# usb_to_uart.net
KiCad netlist of a schematic drawn in Altium Designer
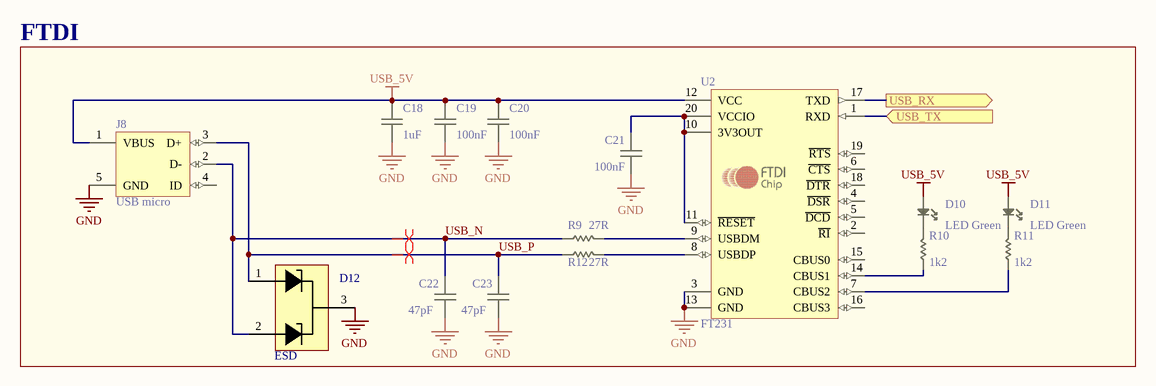
[diagram p0: usb to uart.SchDoc]

(export (version "E")
  (design (tool "Eeschema 10.0.6"))
  (components
    (comp (ref "C18")
      (value "1uF")
      (footprint "C0603")
      (fields (field (name "Comment") "Capacitor 0603"))
      (libsource (lib "altium-import") (part "root_1_Capacitor 0603_"))
    )
    (comp (ref "C19")
      (value "100nF")
      (footprint "C0603")
      (fields (field (name "Comment") "Capacitor 0603"))
      (libsource (lib "altium-import") (part "root_1_Capacitor 0603_"))
    )
    (comp (ref "C20")
      (value "100nF")
      (footprint "C0603")
      (fields (field (name "Comment") "Capacitor 0603"))
      (libsource (lib "altium-import") (part "root_1_Capacitor 0603_"))
    )
    (comp (ref "C21")
      (value "100nF")
      (footprint "C0603")
      (fields (field (name "Comment") "Capacitor 0603"))
      (libsource (lib "altium-import") (part "root_1_Capacitor 0603_"))
    )
    (comp (ref "C22")
      (value "47pF")
      (footprint "C0603")
      (fields (field (name "Comment") "Capacitor 0603"))
      (libsource (lib "altium-import") (part "root_1_Capacitor 0603_"))
    )
    (comp (ref "C23")
      (value "47pF")
      (footprint "C0603")
      (fields (field (name "Comment") "Capacitor 0603"))
      (libsource (lib "altium-import") (part "root_1_Capacitor 0603_"))
    )
    (comp (ref "D10")
      (value "LED Green")
      (footprint "L0603 GREEN")
      (libsource (lib "altium-import") (part "root_3_LED 0603 Green_"))
    )
    (comp (ref "D11")
      (value "LED Green")
      (footprint "L0603 GREEN")
      (libsource (lib "altium-import") (part "root_3_LED 0603 Green_"))
    )
    (comp (ref "D12")
      (value "ESD")
      (footprint "ESD protection")
      (description "PESD3V3S2UAT")
      (libsource (lib "Transistors") (part "ESD protection 3.3V"))
    )
    (comp (ref "J8")
      (value "USB micro")
      (footprint "USB micro")
      (libsource (lib "altium-import") (part "root_0_USB micro_"))
    )
    (comp (ref "R9")
      (value "27R")
      (footprint "R0603")
      (fields (field (name "Comment") "Resistor 0603"))
      (libsource (lib "altium-import") (part "root_0_Resistor 0603_"))
    )
    (comp (ref "R10")
      (value "1k2")
      (footprint "R0603")
      (fields (field (name "Comment") "Resistor 0603"))
      (libsource (lib "altium-import") (part "root_1_Resistor 0603_"))
    )
    (comp (ref "R11")
      (value "1k2")
      (footprint "R0603")
      (fields (field (name "Comment") "Resistor 0603"))
      (libsource (lib "altium-import") (part "root_1_Resistor 0603_"))
    )
    (comp (ref "R12")
      (value "27R")
      (footprint "R0603")
      (fields (field (name "Comment") "Resistor 0603"))
      (libsource (lib "altium-import") (part "root_0_Resistor 0603_"))
    )
    (comp (ref "U2")
      (value "FT231")
      (footprint "FTDI")
      (description "USB to UART")
      (libsource (lib "altium-import") (part "root_0_FTDI_"))
    )
  )
  (nets
    (net (code "1") (name "/USB_N") (class "Default")
      (node (ref "C22") (pin "2") (pinfunction "2_2") (pintype "passive"))
      (node (ref "D12") (pin "2") (pintype "passive"))
      (node (ref "J8") (pin "2") (pinfunction "D-_2") (pintype "bidirectional"))
      (node (ref "R9") (pin "1") (pinfunction "1_1") (pintype "passive"))
    )
    (net (code "2") (name "/USB_P") (class "Default")
      (node (ref "C23") (pin "2") (pinfunction "2_2") (pintype "passive"))
      (node (ref "D12") (pin "1") (pintype "passive"))
      (node (ref "J8") (pin "3") (pinfunction "D+_3") (pintype "bidirectional"))
      (node (ref "R12") (pin "1") (pinfunction "1_1") (pintype "passive"))
    )
    (net (code "3") (name "/USB_RX") (class "Default")
      (node (ref "U2") (pin "17") (pinfunction "TXD_17") (pintype "output"))
    )
    (net (code "4") (name "/USB_TX") (class "Default")
      (node (ref "U2") (pin "1") (pinfunction "RXD_1") (pintype "input"))
    )
    (net (code "5") (name "GND") (class "Default")
      (node (ref "C18") (pin "1") (pinfunction "1_1") (pintype "passive"))
      (node (ref "C19") (pin "1") (pinfunction "1_1") (pintype "passive"))
      (node (ref "C20") (pin "1") (pinfunction "1_1") (pintype "passive"))
      (node (ref "C21") (pin "1") (pinfunction "1_1") (pintype "passive"))
      (node (ref "C22") (pin "1") (pinfunction "1_1") (pintype "passive"))
      (node (ref "C23") (pin "1") (pinfunction "1_1") (pintype "passive"))
      (node (ref "D12") (pin "3") (pintype "passive"))
      (node (ref "J8") (pin "5") (pinfunction "GND_5") (pintype "passive"))
      (node (ref "U2") (pin "13") (pinfunction "GND_13") (pintype "passive"))
      (node (ref "U2") (pin "3") (pinfunction "GND_3") (pintype "passive"))
    )
    (net (code "6") (name "Net-(D10-Pad2)") (class "Default")
      (node (ref "D10") (pin "2") (pinfunction "2_2") (pintype "passive"))
      (node (ref "R10") (pin "2") (pinfunction "2_2") (pintype "passive"))
    )
    (net (code "7") (name "Net-(D11-Pad2)") (class "Default")
      (node (ref "D11") (pin "2") (pinfunction "2_2") (pintype "passive"))
      (node (ref "R11") (pin "2") (pinfunction "2_2") (pintype "passive"))
    )
    (net (code "8") (name "Net-(U2-3V3OUT)") (class "Default")
      (node (ref "C21") (pin "2") (pinfunction "2_2") (pintype "passive"))
      (node (ref "U2") (pin "10") (pinfunction "3V3OUT_10") (pintype "passive"))
      (node (ref "U2") (pin "11") (pinfunction "~{RESET}_11") (pintype "bidirectional"))
      (node (ref "U2") (pin "20") (pinfunction "VCCIO_20") (pintype "passive"))
    )
    (net (code "9") (name "Net-(U2-CBUS1)") (class "Default")
      (node (ref "R10") (pin "1") (pinfunction "1_1") (pintype "passive"))
      (node (ref "U2") (pin "14") (pinfunction "CBUS1_14") (pintype "bidirectional"))
    )
    (net (code "10") (name "Net-(U2-CBUS2)") (class "Default")
      (node (ref "R11") (pin "1") (pinfunction "1_1") (pintype "passive"))
      (node (ref "U2") (pin "7") (pinfunction "CBUS2_7") (pintype "bidirectional"))
    )
    (net (code "11") (name "Net-(U2-USBDM)") (class "Default")
      (node (ref "R9") (pin "2") (pinfunction "2_2") (pintype "passive"))
      (node (ref "U2") (pin "9") (pinfunction "USBDM_9") (pintype "bidirectional"))
    )
    (net (code "12") (name "Net-(U2-USBDP)") (class "Default")
      (node (ref "R12") (pin "2") (pinfunction "2_2") (pintype "passive"))
      (node (ref "U2") (pin "8") (pinfunction "USBDP_8") (pintype "bidirectional"))
    )
    (net (code "13") (name "USB_5V") (class "Default")
      (node (ref "C18") (pin "2") (pinfunction "2_2") (pintype "passive"))
      (node (ref "C19") (pin "2") (pinfunction "2_2") (pintype "passive"))
      (node (ref "C20") (pin "2") (pinfunction "2_2") (pintype "passive"))
      (node (ref "D10") (pin "1") (pinfunction "1_1") (pintype "passive"))
      (node (ref "D11") (pin "1") (pinfunction "1_1") (pintype "passive"))
      (node (ref "J8") (pin "1") (pinfunction "VBUS_1") (pintype "passive"))
      (node (ref "U2") (pin "12") (pinfunction "VCC_12") (pintype "passive"))
    )
    (net (code "14") (name "unconnected-(J8-ID-Pad4)") (class "Default")
      (node (ref "J8") (pin "4") (pinfunction "ID_4") (pintype "bidirectional"))
    )
    (net (code "15") (name "unconnected-(U2-CBUS0-Pad15)") (class "Default")
      (node (ref "U2") (pin "15") (pinfunction "CBUS0_15") (pintype "bidirectional"))
    )
    (net (code "16") (name "unconnected-(U2-CBUS3-Pad16)") (class "Default")
      (node (ref "U2") (pin "16") (pinfunction "CBUS3_16") (pintype "bidirectional"))
    )
    (net (code "17") (name "unconnected-(U2-~{CTS}-Pad6)") (class "Default")
      (node (ref "U2") (pin "6") (pinfunction "~{CTS}_6") (pintype "bidirectional"))
    )
    (net (code "18") (name "unconnected-(U2-~{DCD}-Pad5)") (class "Default")
      (node (ref "U2") (pin "5") (pinfunction "~{DCD}_5") (pintype "bidirectional"))
    )
    (net (code "19") (name "unconnected-(U2-~{DSR}-Pad4)") (class "Default")
      (node (ref "U2") (pin "4") (pinfunction "~{DSR}_4") (pintype "bidirectional"))
    )
    (net (code "20") (name "unconnected-(U2-~{DTR}-Pad18)") (class "Default")
      (node (ref "U2") (pin "18") (pinfunction "~{DTR}_18") (pintype "bidirectional"))
    )
    (net (code "21") (name "unconnected-(U2-~{RI}-Pad2)") (class "Default")
      (node (ref "U2") (pin "2") (pinfunction "~{RI}_2") (pintype "bidirectional"))
    )
    (net (code "22") (name "unconnected-(U2-~{RTS}-Pad19)") (class "Default")
      (node (ref "U2") (pin "19") (pinfunction "~{RTS}_19") (pintype "bidirectional"))
    )
  )
)
